# LCD_UC1601.net
KiCad netlist of a schematic drawn in Altium Designer
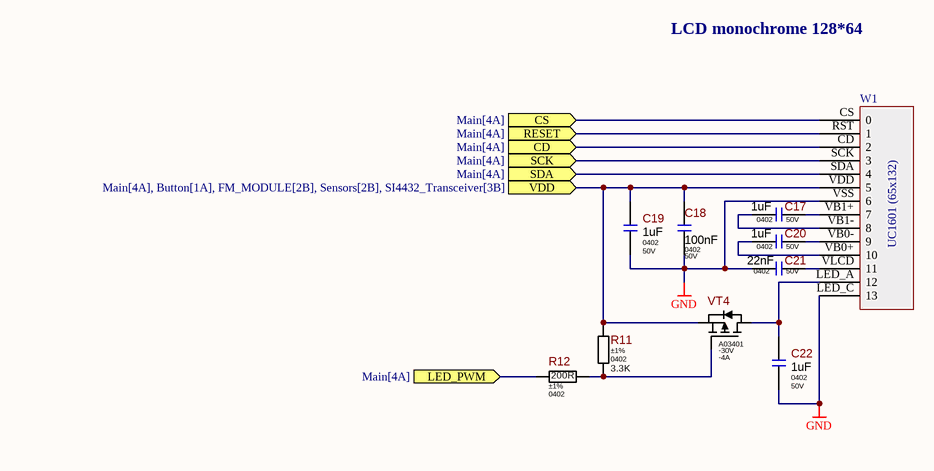
[diagram p0: LCD_UC1601.SchDoc]

(export (version "E")
  (design (tool "Eeschema 10.0.6"))
  (components
    (comp (ref "C17")
      (value "1uF")
      (footprint "Cap_0402")
      (description "1uF 50V  ±25% 0402 Ceramic Capacitor")
      (fields
        (field (name "TOLERANCE") "±25%")
        (field (name "PACKAGE") "0402")
        (field (name "VOLTAGE") "50V")
      )
      (libsource (lib "Capacitors") (part "Cap_0402_1uF"))
    )
    (comp (ref "C18")
      (value "100nF")
      (footprint "Cap_0402")
      (description "100nF 50V  ±25% 0402 Ceramic Capacitor")
      (fields
        (field (name "TOLERANCE") "±25%")
        (field (name "PACKAGE") "0402")
        (field (name "VOLTAGE") "50V")
      )
      (libsource (lib "Capacitors") (part "Cap_0402_100nF"))
    )
    (comp (ref "C19")
      (value "1uF")
      (footprint "Cap_0402")
      (description "1uF 50V  ±25% 0402 Ceramic Capacitor")
      (fields
        (field (name "TOLERANCE") "±25%")
        (field (name "PACKAGE") "0402")
        (field (name "VOLTAGE") "50V")
      )
      (libsource (lib "Capacitors") (part "Cap_0402_1uF"))
    )
    (comp (ref "C20")
      (value "1uF")
      (footprint "Cap_0402")
      (description "1uF 50V  ±25% 0402 Ceramic Capacitor")
      (fields
        (field (name "TOLERANCE") "±25%")
        (field (name "PACKAGE") "0402")
        (field (name "VOLTAGE") "50V")
      )
      (libsource (lib "Capacitors") (part "Cap_0402_1uF"))
    )
    (comp (ref "C21")
      (value "22nF")
      (footprint "Cap_0402")
      (description "22nF 50V  ±25% 0402 Ceramic Capacitor")
      (fields
        (field (name "TOLERANCE") "±25%")
        (field (name "PACKAGE") "0402")
        (field (name "VOLTAGE") "50V")
      )
      (libsource (lib "Capacitors") (part "Cap_0402_22nF"))
    )
    (comp (ref "C22")
      (value "1uF")
      (footprint "Cap_0402")
      (description "1uF 50V  ±25% 0402 Ceramic Capacitor")
      (fields
        (field (name "TOLERANCE") "±25%")
        (field (name "PACKAGE") "0402")
        (field (name "VOLTAGE") "50V")
      )
      (libsource (lib "Capacitors") (part "Cap_0402_1uF"))
    )
    (comp (ref "R11")
      (value "3.3K")
      (footprint "Res_0402")
      (description "±1% 1/16W 0402")
      (fields
        (field (name "VOLTAGE") "50V")
        (field (name "TOLERANCE") "±1%")
        (field (name "PACKAGE") "0402")
        (field (name "Comment") "Res_0402_3.3K")
      )
      (libsource (lib "Resistors") (part "Res_0402_3.3K"))
    )
    (comp (ref "R12")
      (value "200R")
      (footprint "Res_0402")
      (description "±1% 1/16W 0402")
      (fields
        (field (name "VOLTAGE") "50V")
        (field (name "TOLERANCE") "±1%")
        (field (name "PACKAGE") "0402")
        (field (name "Comment") "Res_0402_200R")
      )
      (libsource (lib "Resistors") (part "Res_0402_200R"))
    )
    (comp (ref "VT4")
      (value "A03401")
      (footprint "SOT-23")
      (description "-30V, -4A max P-Channel  MOSFET, 60mOhm @ Vgs = -4.5V")
      (fields (field (name "NAME") "A03401") (field (name "VDS") "-30V") (field (name "ID") "-4A"))
      (libsource (lib "Transistors") (part "A03401"))
    )
    (comp (ref "W1")
      (value "LCD_UC1601s")
      (footprint "LCD_connector_14PIN_0.5mm")
      (libsource (lib "LCD") (part "LCD_UC1601s"))
    )
  )
  (nets
    (net (code "1") (name "/CD") (class "Default")
      (node (ref "W1") (pin "CD") (pinfunction "2_CD") (pintype "passive"))
    )
    (net (code "2") (name "/CS") (class "Default")
      (node (ref "W1") (pin "CS") (pinfunction "0_CS") (pintype "passive"))
    )
    (net (code "3") (name "/LED_PWM") (class "Default") (node (ref "R12") (pin "1") (pintype "passive")))
    (net (code "4") (name "/RESET") (class "Default")
      (node (ref "W1") (pin "RST") (pinfunction "1_RST") (pintype "passive"))
    )
    (net (code "5") (name "/SCK") (class "Default")
      (node (ref "W1") (pin "SCK") (pinfunction "3_SCK") (pintype "passive"))
    )
    (net (code "6") (name "/SDA") (class "Default")
      (node (ref "W1") (pin "SDA") (pinfunction "4_SDA") (pintype "passive"))
    )
    (net (code "7") (name "/VDD") (class "Default")
      (node (ref "C18") (pin "1") (pinfunction "1_1") (pintype "passive"))
      (node (ref "C19") (pin "1") (pinfunction "1_1") (pintype "passive"))
      (node (ref "R11") (pin "2") (pintype "passive"))
      (node (ref "VT4") (pin "2") (pinfunction "S_2") (pintype "passive"))
      (node (ref "W1") (pin "VDD") (pinfunction "5_VDD") (pintype "passive"))
    )
    (net (code "8") (name "GND") (class "Default")
      (node (ref "C18") (pin "2") (pinfunction "2_2") (pintype "passive"))
      (node (ref "C19") (pin "2") (pinfunction "2_2") (pintype "passive"))
      (node (ref "C21") (pin "1") (pinfunction "1_1") (pintype "passive"))
      (node (ref "C22") (pin "2") (pinfunction "2_2") (pintype "passive"))
      (node (ref "W1") (pin "LED_C") (pinfunction "13_LED_C") (pintype "passive"))
      (node (ref "W1") (pin "VSS") (pinfunction "6_VSS") (pintype "passive"))
    )
    (net (code "9") (name "Net-(VT4-D)") (class "Default")
      (node (ref "C22") (pin "1") (pinfunction "1_1") (pintype "passive"))
      (node (ref "VT4") (pin "3") (pinfunction "D_3") (pintype "passive"))
      (node (ref "W1") (pin "LED_A") (pinfunction "12_LED_A") (pintype "passive"))
    )
    (net (code "10") (name "Net-(VT4-G)") (class "Default")
      (node (ref "R11") (pin "1") (pintype "passive"))
      (node (ref "R12") (pin "2") (pintype "passive"))
      (node (ref "VT4") (pin "1") (pinfunction "G_1") (pintype "passive"))
    )
    (net (code "11") (name "Net-(W1-7)") (class "Default")
      (node (ref "C17") (pin "2") (pinfunction "2_2") (pintype "passive"))
      (node (ref "W1") (pin "VB1+") (pinfunction "7_VB1+") (pintype "passive"))
    )
    (net (code "12") (name "Net-(W1-8)") (class "Default")
      (node (ref "C17") (pin "1") (pinfunction "1_1") (pintype "passive"))
      (node (ref "W1") (pin "VB1-") (pinfunction "8_VB1-") (pintype "passive"))
    )
    (net (code "13") (name "Net-(W1-9)") (class "Default")
      (node (ref "C20") (pin "2") (pinfunction "2_2") (pintype "passive"))
      (node (ref "W1") (pin "VB0-") (pinfunction "9_VB0-") (pintype "passive"))
    )
    (net (code "14") (name "Net-(W1-10)") (class "Default")
      (node (ref "C20") (pin "1") (pinfunction "1_1") (pintype "passive"))
      (node (ref "W1") (pin "VB0+") (pinfunction "10_VB0+") (pintype "passive"))
    )
    (net (code "15") (name "Net-(W1-11)") (class "Default")
      (node (ref "C21") (pin "2") (pinfunction "2_2") (pintype "passive"))
      (node (ref "W1") (pin "VLCD") (pinfunction "11_VLCD") (pintype "passive"))
    )
  )
)
